# TS.net
KiCad netlist of a schematic drawn in Altium Designer
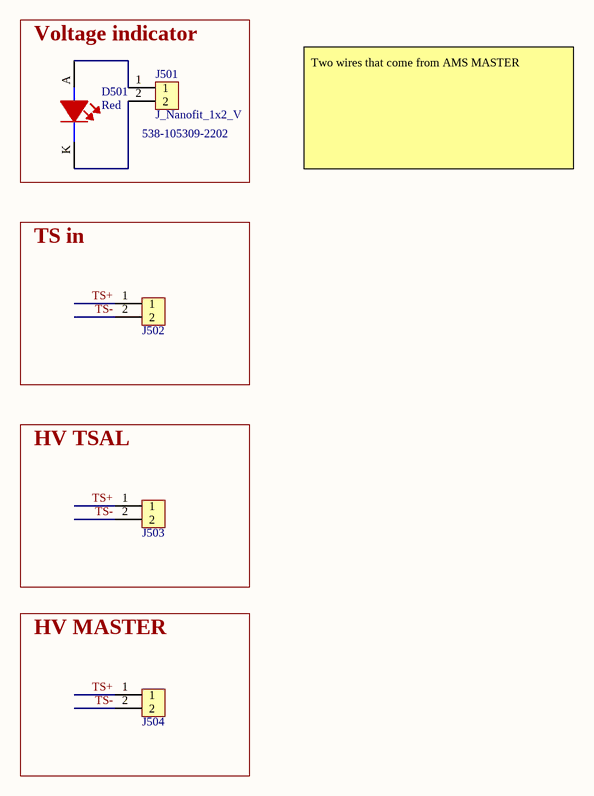
[diagram p0: TS.SchDoc]

(export (version "E")
  (design (tool "Eeschema 10.0.6"))
  (components
    (comp (ref "D501")
      (value "150080RS75000")
      (footprint "LED-THT/WE/D3.9H10.5")
      (description "0805(H=0.8mm) 红色 高亮 λD=625nm VF=2V IF=30mA PD=72mW")
      (fields (field (name "COLOR") "Red") (field (name ".CREATOR") "DR"))
      (libsource (lib "Semiconductor") (part "LEDRS-THT"))
    )
    (comp (ref "J501")
      (value "J_Nanofit_1x2_V")
      (footprint "J_NanoFit_1X2_V")
      (fields
        (field (name "MANUFACTURER") "Molex")
        (field (name "MANUFACTURER PART NUMBER") "1053092202")
        (field (name "SUPPLIER PART NUMBER 1") "538-105309-2202")
      )
      (libsource (lib "Electromechanical") (part "J_Nanofit_1x2_V"))
    )
    (comp (ref "J502")
      (value "436500215")
      (footprint "J_MicroFit_2x1")
      (description "Header 1 Row Vertical Polarizing Peg 2 Pin SMT/Glow Wire Compatible Tin Plate")
      (libsource (lib "Electromechanical") (part "J_MicroFit_2x1"))
    )
    (comp (ref "J503")
      (value "436500215")
      (footprint "J_MicroFit_2x1")
      (description "Header 1 Row Vertical Polarizing Peg 2 Pin SMT/Glow Wire Compatible Tin Plate")
      (libsource (lib "Electromechanical") (part "J_MicroFit_2x1"))
    )
    (comp (ref "J504")
      (value "436500215")
      (footprint "J_MicroFit_2x1")
      (description "Header 1 Row Vertical Polarizing Peg 2 Pin SMT/Glow Wire Compatible Tin Plate")
      (libsource (lib "Electromechanical") (part "J_MicroFit_2x1"))
    )
  )
  (nets
    (net (code "1") (name "/TS+") (class "Default")
      (node (ref "J502") (pin "1") (pinfunction "1_1") (pintype "passive"))
      (node (ref "J503") (pin "1") (pinfunction "1_1") (pintype "passive"))
      (node (ref "J504") (pin "1") (pinfunction "1_1") (pintype "passive"))
    )
    (net (code "2") (name "/TS-") (class "Default")
      (node (ref "J502") (pin "2") (pinfunction "2_2") (pintype "passive"))
      (node (ref "J503") (pin "2") (pinfunction "2_2") (pintype "passive"))
      (node (ref "J504") (pin "2") (pinfunction "2_2") (pintype "passive"))
    )
    (net (code "3") (name "Net-(D501-PadA)") (class "Default")
      (node (ref "D501") (pin "A") (pinfunction "A_A") (pintype "passive"))
      (node (ref "J501") (pin "1") (pinfunction "1_1") (pintype "passive"))
    )
    (net (code "4") (name "Net-(D501-PadK)") (class "Default")
      (node (ref "D501") (pin "K") (pinfunction "K_K") (pintype "passive"))
      (node (ref "J501") (pin "2") (pinfunction "2_2") (pintype "passive"))
    )
  )
)
